# myPowerSatBoard.net
KiCad netlist of a schematic drawn in EAGLE
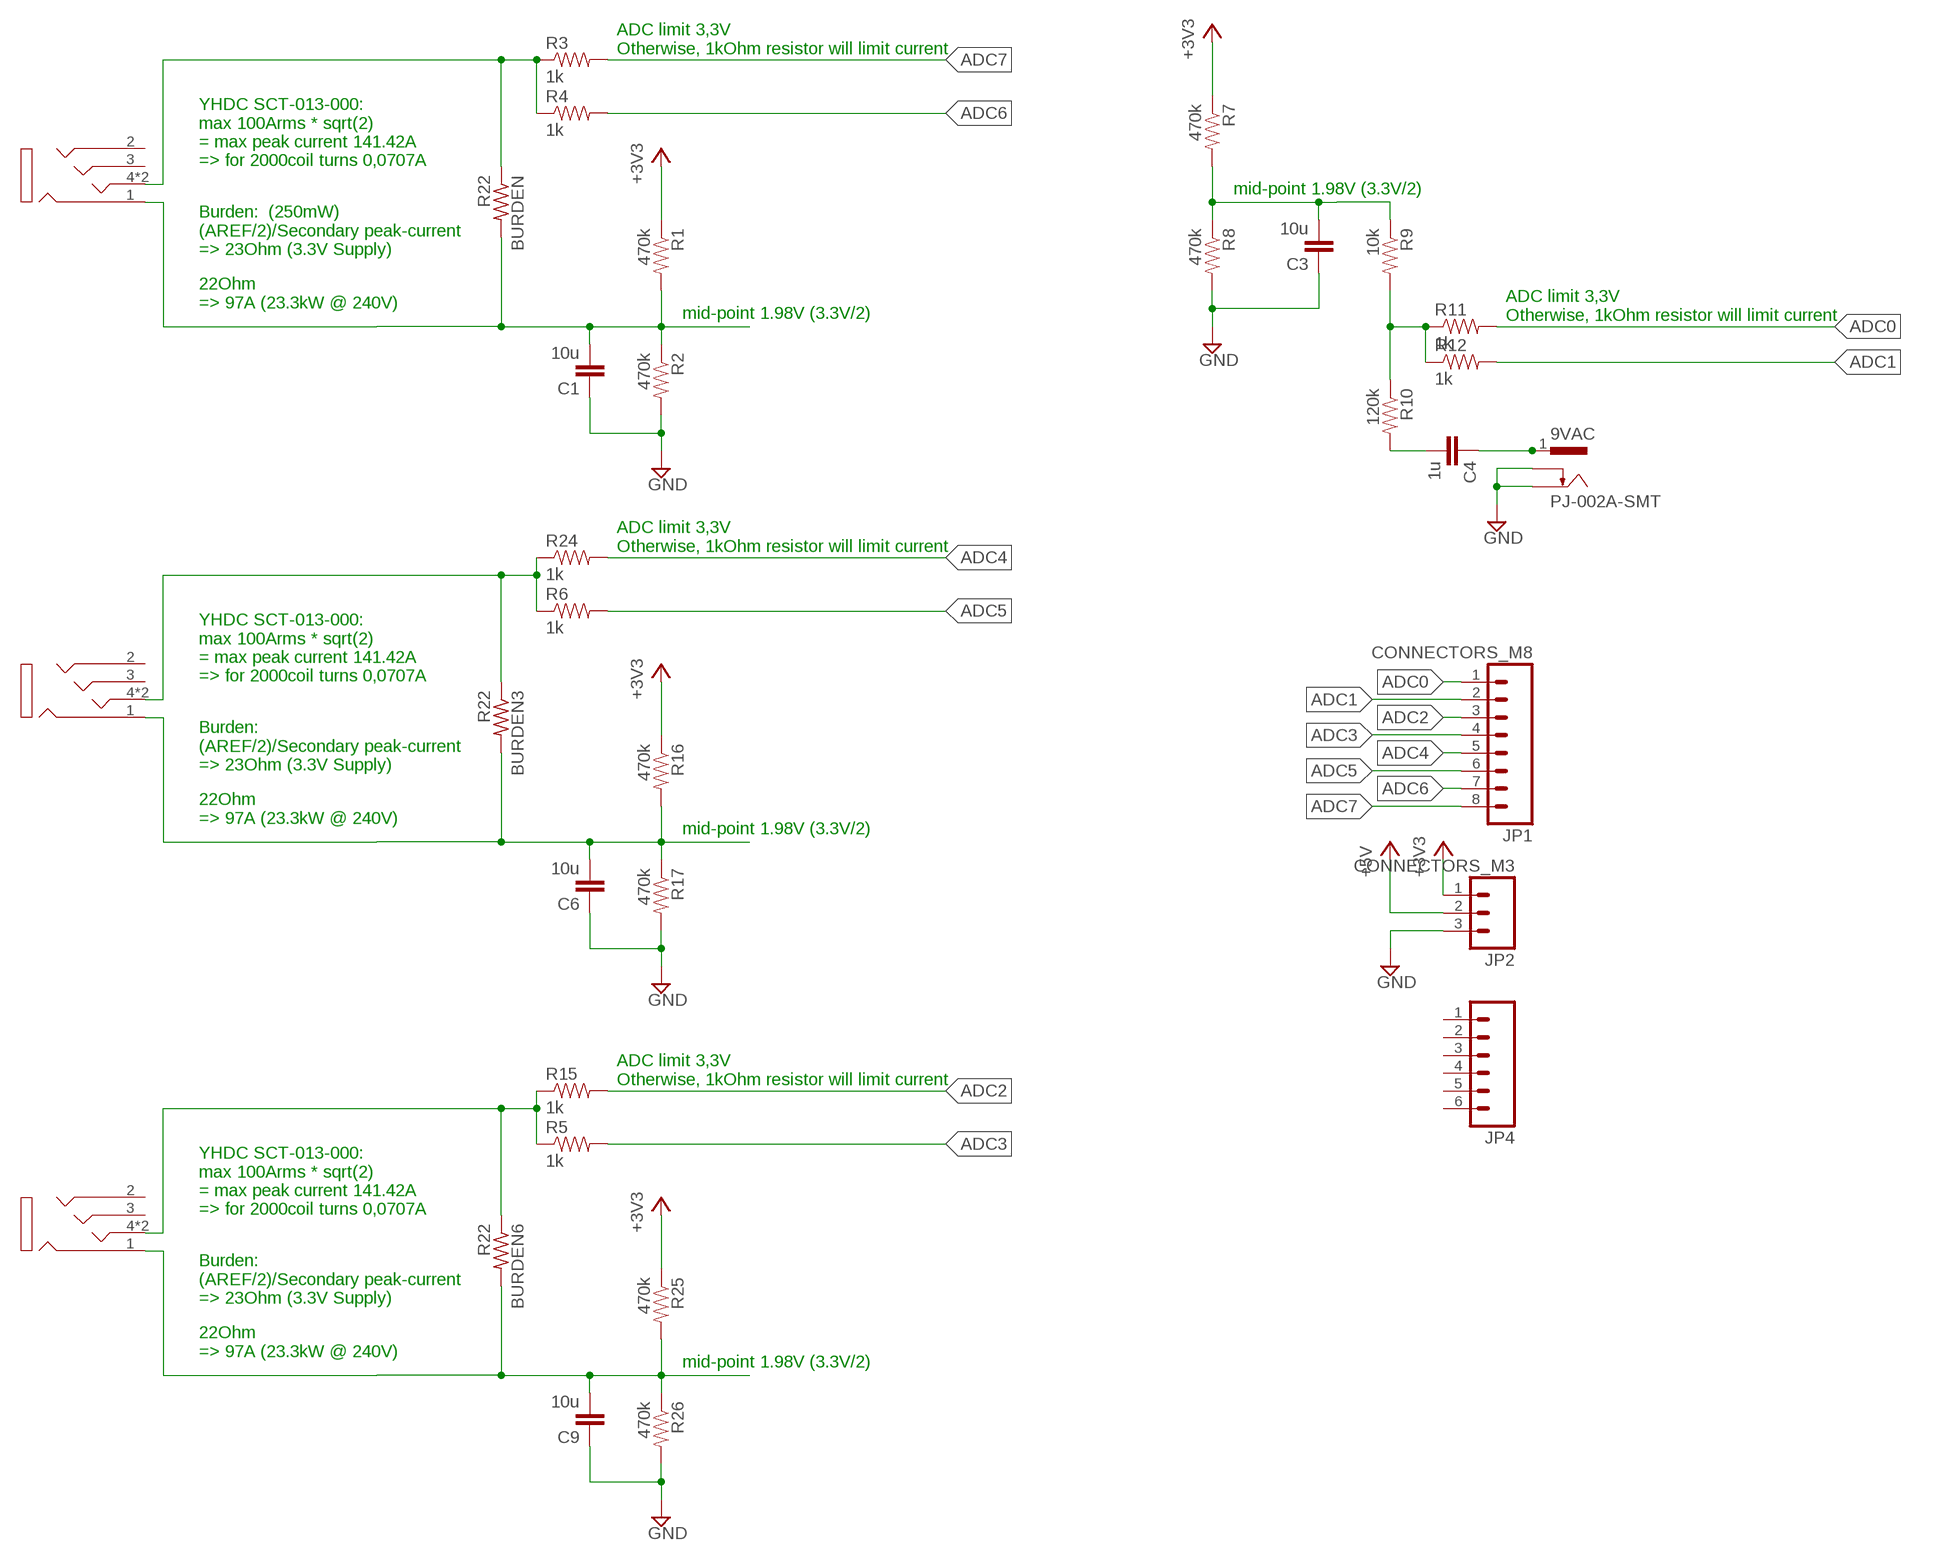
[diagram p0: schematic, sheet 1]

(export (version "E")
  (design (tool "Eeschema 10.0.6"))
  (components
    (comp (ref "9VAC")
      (value "PJ-002A-SMT")
      (footprint "eagle-import:CUI_PJ-002B-SMT")
      (libsource (lib "eagle-import") (part "PJ-002A-SMT"))
    )
    (comp (ref "BURDEN")
      (value "R22")
      (footprint "eagle-import:R0805")
      (libsource (lib "eagle-import") (part "R-US_R0805"))
    )
    (comp (ref "BURDEN3")
      (value "R22")
      (footprint "eagle-import:R0805")
      (libsource (lib "eagle-import") (part "R-US_R0805"))
    )
    (comp (ref "BURDEN6")
      (value "R22")
      (footprint "eagle-import:R0805")
      (libsource (lib "eagle-import") (part "R-US_R0805"))
    )
    (comp (ref "C1")
      (value "10u")
      (footprint "eagle-import:0603-CAP")
      (libsource (lib "eagle-import") (part "CAP0603-CAP"))
    )
    (comp (ref "C3")
      (value "10u")
      (footprint "eagle-import:0603-CAP")
      (libsource (lib "eagle-import") (part "CAP0603-CAP"))
    )
    (comp (ref "C4")
      (value "1u")
      (footprint "eagle-import:0603-CAP")
      (libsource (lib "eagle-import") (part "CAP0603-CAP"))
    )
    (comp (ref "C6")
      (value "10u")
      (footprint "eagle-import:0603-CAP")
      (libsource (lib "eagle-import") (part "CAP0603-CAP"))
    )
    (comp (ref "C9")
      (value "10u")
      (footprint "eagle-import:0603-CAP")
      (libsource (lib "eagle-import") (part "CAP0603-CAP"))
    )
    (comp (ref "CT1")
      (value "1503_13")
      (footprint "eagle-import:1503-03")
      (libsource (lib "eagle-import") (part "1503_13"))
    )
    (comp (ref "CT4")
      (value "1503_13")
      (footprint "eagle-import:1503-03")
      (libsource (lib "eagle-import") (part "1503_13"))
    )
    (comp (ref "CT7")
      (value "1503_13")
      (footprint "eagle-import:1503-03")
      (libsource (lib "eagle-import") (part "1503_13"))
    )
    (comp (ref "JP1")
      (value "CONNECTORS_M8")
      (footprint "eagle-import:CONNECTORS_1X8")
      (libsource (lib "eagle-import") (part "CONNECTORS_M8"))
    )
    (comp (ref "JP2")
      (value "CONNECTORS_M3")
      (footprint "eagle-import:CONNECTORS_1X3")
      (libsource (lib "eagle-import") (part "CONNECTORS_M3"))
    )
    (comp (ref "JP4")
      (value "CONNECTORS_M06SIP")
      (footprint "eagle-import:CONNECTORS_1X06")
      (libsource (lib "eagle-import") (part "CONNECTORS_M06SIP"))
    )
    (comp (ref "R1")
      (value "470k")
      (footprint "eagle-import:0603-RES")
      (libsource (lib "eagle-import") (part "RESISTOR0603-RES"))
    )
    (comp (ref "R2")
      (value "470k")
      (footprint "eagle-import:0603-RES")
      (libsource (lib "eagle-import") (part "RESISTOR0603-RES"))
    )
    (comp (ref "R3")
      (value "1k")
      (footprint "eagle-import:0603-RES")
      (libsource (lib "eagle-import") (part "RESISTOR0603-RES"))
    )
    (comp (ref "R4")
      (value "1k")
      (footprint "eagle-import:0603-RES")
      (libsource (lib "eagle-import") (part "RESISTOR0603-RES"))
    )
    (comp (ref "R5")
      (value "1k")
      (footprint "eagle-import:0603-RES")
      (libsource (lib "eagle-import") (part "RESISTOR0603-RES"))
    )
    (comp (ref "R6")
      (value "1k")
      (footprint "eagle-import:0603-RES")
      (libsource (lib "eagle-import") (part "RESISTOR0603-RES"))
    )
    (comp (ref "R7")
      (value "470k")
      (footprint "eagle-import:0603-RES")
      (libsource (lib "eagle-import") (part "RESISTOR0603-RES"))
    )
    (comp (ref "R8")
      (value "470k")
      (footprint "eagle-import:0603-RES")
      (libsource (lib "eagle-import") (part "RESISTOR0603-RES"))
    )
    (comp (ref "R9")
      (value "10k")
      (footprint "eagle-import:0603-RES")
      (libsource (lib "eagle-import") (part "RESISTOR0603-RES"))
    )
    (comp (ref "R10")
      (value "120k")
      (footprint "eagle-import:0603-RES")
      (libsource (lib "eagle-import") (part "RESISTOR0603-RES"))
    )
    (comp (ref "R11")
      (value "1k")
      (footprint "eagle-import:0603-RES")
      (libsource (lib "eagle-import") (part "RESISTOR0603-RES"))
    )
    (comp (ref "R12")
      (value "1k")
      (footprint "eagle-import:0603-RES")
      (libsource (lib "eagle-import") (part "RESISTOR0603-RES"))
    )
    (comp (ref "R15")
      (value "1k")
      (footprint "eagle-import:0603-RES")
      (libsource (lib "eagle-import") (part "RESISTOR0603-RES"))
    )
    (comp (ref "R16")
      (value "470k")
      (footprint "eagle-import:0603-RES")
      (libsource (lib "eagle-import") (part "RESISTOR0603-RES"))
    )
    (comp (ref "R17")
      (value "470k")
      (footprint "eagle-import:0603-RES")
      (libsource (lib "eagle-import") (part "RESISTOR0603-RES"))
    )
    (comp (ref "R24")
      (value "1k")
      (footprint "eagle-import:0603-RES")
      (libsource (lib "eagle-import") (part "RESISTOR0603-RES"))
    )
    (comp (ref "R25")
      (value "470k")
      (footprint "eagle-import:0603-RES")
      (libsource (lib "eagle-import") (part "RESISTOR0603-RES"))
    )
    (comp (ref "R26")
      (value "470k")
      (footprint "eagle-import:0603-RES")
      (libsource (lib "eagle-import") (part "RESISTOR0603-RES"))
    )
  )
  (nets
    (net (code "1") (name "+3V3") (class "Default")
      (node (ref "JP2") (pin "1") (pinfunction "1_1") (pintype "passive"))
      (node (ref "R1") (pin "1") (pinfunction "1_1") (pintype "passive"))
      (node (ref "R16") (pin "1") (pinfunction "1_1") (pintype "passive"))
      (node (ref "R25") (pin "1") (pinfunction "1_1") (pintype "passive"))
      (node (ref "R7") (pin "1") (pinfunction "1_1") (pintype "passive"))
    )
    (net (code "2") (name "+5V") (class "Default")
      (node (ref "JP2") (pin "2") (pinfunction "2_2") (pintype "passive"))
    )
    (net (code "3") (name "ADC0") (class "Default")
      (node (ref "JP1") (pin "1") (pinfunction "1_1") (pintype "passive"))
      (node (ref "R11") (pin "2") (pinfunction "2_2") (pintype "passive"))
    )
    (net (code "4") (name "ADC1") (class "Default")
      (node (ref "JP1") (pin "2") (pinfunction "2_2") (pintype "passive"))
      (node (ref "R12") (pin "2") (pinfunction "2_2") (pintype "passive"))
    )
    (net (code "5") (name "ADC2") (class "Default")
      (node (ref "JP1") (pin "3") (pinfunction "3_3") (pintype "passive"))
      (node (ref "R15") (pin "2") (pinfunction "2_2") (pintype "passive"))
    )
    (net (code "6") (name "ADC3") (class "Default")
      (node (ref "JP1") (pin "4") (pinfunction "4_4") (pintype "passive"))
      (node (ref "R5") (pin "2") (pinfunction "2_2") (pintype "passive"))
    )
    (net (code "7") (name "ADC4") (class "Default")
      (node (ref "JP1") (pin "5") (pinfunction "5_5") (pintype "passive"))
      (node (ref "R24") (pin "2") (pinfunction "2_2") (pintype "passive"))
    )
    (net (code "8") (name "ADC5") (class "Default")
      (node (ref "JP1") (pin "6") (pinfunction "6_6") (pintype "passive"))
      (node (ref "R6") (pin "2") (pinfunction "2_2") (pintype "passive"))
    )
    (net (code "9") (name "ADC6") (class "Default")
      (node (ref "JP1") (pin "7") (pinfunction "7_7") (pintype "passive"))
      (node (ref "R4") (pin "2") (pinfunction "2_2") (pintype "passive"))
    )
    (net (code "10") (name "ADC7") (class "Default")
      (node (ref "JP1") (pin "8") (pinfunction "8_8") (pintype "passive"))
      (node (ref "R3") (pin "2") (pinfunction "2_2") (pintype "passive"))
    )
    (net (code "11") (name "GND") (class "Default")
      (node (ref "9VAC") (pin "3") (pinfunction "3_3") (pintype "passive"))
      (node (ref "9VAC") (pin "4") (pinfunction "4_4") (pintype "passive"))
      (node (ref "C1") (pin "1") (pinfunction "1_1") (pintype "passive"))
      (node (ref "C3") (pin "1") (pinfunction "1_1") (pintype "passive"))
      (node (ref "C6") (pin "1") (pinfunction "1_1") (pintype "passive"))
      (node (ref "C9") (pin "1") (pinfunction "1_1") (pintype "passive"))
      (node (ref "JP2") (pin "3") (pinfunction "3_3") (pintype "passive"))
      (node (ref "R17") (pin "2") (pinfunction "2_2") (pintype "passive"))
      (node (ref "R2") (pin "2") (pinfunction "2_2") (pintype "passive"))
      (node (ref "R26") (pin "2") (pinfunction "2_2") (pintype "passive"))
      (node (ref "R8") (pin "2") (pinfunction "2_2") (pintype "passive"))
    )
    (net (code "12") (name "Net-(9VAC-Pad1)") (class "Default")
      (node (ref "9VAC") (pin "1") (pinfunction "1_1") (pintype "passive"))
      (node (ref "9VAC") (pin "2") (pinfunction "2_2") (pintype "passive"))
      (node (ref "C4") (pin "1") (pinfunction "1_1") (pintype "passive"))
    )
    (net (code "13") (name "Net-(BURDEN-Pad1)") (class "Default")
      (node (ref "BURDEN") (pin "1") (pinfunction "1_1") (pintype "passive"))
      (node (ref "CT1") (pin "4") (pinfunction "4_4") (pintype "bidirectional"))
      (node (ref "CT1") (pin "4-2") (pinfunction "4_4-2") (pintype "bidirectional"))
      (node (ref "R3") (pin "1") (pinfunction "1_1") (pintype "passive"))
      (node (ref "R4") (pin "1") (pinfunction "1_1") (pintype "passive"))
    )
    (net (code "14") (name "Net-(BURDEN-Pad2)") (class "Default")
      (node (ref "BURDEN") (pin "2") (pinfunction "2_2") (pintype "passive"))
      (node (ref "C1") (pin "2") (pinfunction "2_2") (pintype "passive"))
      (node (ref "CT1") (pin "1") (pinfunction "1_1") (pintype "bidirectional"))
      (node (ref "R1") (pin "2") (pinfunction "2_2") (pintype "passive"))
      (node (ref "R2") (pin "1") (pinfunction "1_1") (pintype "passive"))
    )
    (net (code "15") (name "Net-(BURDEN3-Pad1)") (class "Default")
      (node (ref "BURDEN3") (pin "1") (pinfunction "1_1") (pintype "passive"))
      (node (ref "CT4") (pin "4") (pinfunction "4_4") (pintype "bidirectional"))
      (node (ref "CT4") (pin "4-2") (pinfunction "4_4-2") (pintype "bidirectional"))
      (node (ref "R24") (pin "1") (pinfunction "1_1") (pintype "passive"))
      (node (ref "R6") (pin "1") (pinfunction "1_1") (pintype "passive"))
    )
    (net (code "16") (name "Net-(BURDEN3-Pad2)") (class "Default")
      (node (ref "BURDEN3") (pin "2") (pinfunction "2_2") (pintype "passive"))
      (node (ref "C6") (pin "2") (pinfunction "2_2") (pintype "passive"))
      (node (ref "CT4") (pin "1") (pinfunction "1_1") (pintype "bidirectional"))
      (node (ref "R16") (pin "2") (pinfunction "2_2") (pintype "passive"))
      (node (ref "R17") (pin "1") (pinfunction "1_1") (pintype "passive"))
    )
    (net (code "17") (name "Net-(BURDEN6-Pad1)") (class "Default")
      (node (ref "BURDEN6") (pin "1") (pinfunction "1_1") (pintype "passive"))
      (node (ref "CT7") (pin "4") (pinfunction "4_4") (pintype "bidirectional"))
      (node (ref "CT7") (pin "4-2") (pinfunction "4_4-2") (pintype "bidirectional"))
      (node (ref "R15") (pin "1") (pinfunction "1_1") (pintype "passive"))
      (node (ref "R5") (pin "1") (pinfunction "1_1") (pintype "passive"))
    )
    (net (code "18") (name "Net-(BURDEN6-Pad2)") (class "Default")
      (node (ref "BURDEN6") (pin "2") (pinfunction "2_2") (pintype "passive"))
      (node (ref "C9") (pin "2") (pinfunction "2_2") (pintype "passive"))
      (node (ref "CT7") (pin "1") (pinfunction "1_1") (pintype "bidirectional"))
      (node (ref "R25") (pin "2") (pinfunction "2_2") (pintype "passive"))
      (node (ref "R26") (pin "1") (pinfunction "1_1") (pintype "passive"))
    )
    (net (code "19") (name "Net-(C3-Pad2)") (class "Default")
      (node (ref "C3") (pin "2") (pinfunction "2_2") (pintype "passive"))
      (node (ref "R7") (pin "2") (pinfunction "2_2") (pintype "passive"))
      (node (ref "R8") (pin "1") (pinfunction "1_1") (pintype "passive"))
      (node (ref "R9") (pin "1") (pinfunction "1_1") (pintype "passive"))
    )
    (net (code "20") (name "Net-(C4-Pad2)") (class "Default")
      (node (ref "C4") (pin "2") (pinfunction "2_2") (pintype "passive"))
      (node (ref "R10") (pin "2") (pinfunction "2_2") (pintype "passive"))
    )
    (net (code "21") (name "Net-(R10-Pad1)") (class "Default")
      (node (ref "R10") (pin "1") (pinfunction "1_1") (pintype "passive"))
      (node (ref "R11") (pin "1") (pinfunction "1_1") (pintype "passive"))
      (node (ref "R12") (pin "1") (pinfunction "1_1") (pintype "passive"))
      (node (ref "R9") (pin "2") (pinfunction "2_2") (pintype "passive"))
    )
    (net (code "22") (name "unconnected-(CT1-Pad2)") (class "Default")
      (node (ref "CT1") (pin "2") (pinfunction "2_2") (pintype "bidirectional"))
    )
    (net (code "23") (name "unconnected-(CT1-Pad3)") (class "Default")
      (node (ref "CT1") (pin "3") (pinfunction "3_3") (pintype "bidirectional"))
    )
    (net (code "24") (name "unconnected-(CT4-Pad2)") (class "Default")
      (node (ref "CT4") (pin "2") (pinfunction "2_2") (pintype "bidirectional"))
    )
    (net (code "25") (name "unconnected-(CT4-Pad3)") (class "Default")
      (node (ref "CT4") (pin "3") (pinfunction "3_3") (pintype "bidirectional"))
    )
    (net (code "26") (name "unconnected-(CT7-Pad2)") (class "Default")
      (node (ref "CT7") (pin "2") (pinfunction "2_2") (pintype "bidirectional"))
    )
    (net (code "27") (name "unconnected-(CT7-Pad3)") (class "Default")
      (node (ref "CT7") (pin "3") (pinfunction "3_3") (pintype "bidirectional"))
    )
    (net (code "28") (name "unconnected-(JP4-Pad1)") (class "Default")
      (node (ref "JP4") (pin "1") (pinfunction "1_1") (pintype "passive"))
    )
    (net (code "29") (name "unconnected-(JP4-Pad2)") (class "Default")
      (node (ref "JP4") (pin "2") (pinfunction "2_2") (pintype "passive"))
    )
    (net (code "30") (name "unconnected-(JP4-Pad3)") (class "Default")
      (node (ref "JP4") (pin "3") (pinfunction "3_3") (pintype "passive"))
    )
    (net (code "31") (name "unconnected-(JP4-Pad4)") (class "Default")
      (node (ref "JP4") (pin "4") (pinfunction "4_4") (pintype "passive"))
    )
    (net (code "32") (name "unconnected-(JP4-Pad5)") (class "Default")
      (node (ref "JP4") (pin "5") (pinfunction "5_5") (pintype "passive"))
    )
    (net (code "33") (name "unconnected-(JP4-Pad6)") (class "Default")
      (node (ref "JP4") (pin "6") (pinfunction "6_6") (pintype "passive"))
    )
  )
)
